# Sch_ma-reflex.net
KiCad netlist of a schematic drawn in EasyEDA
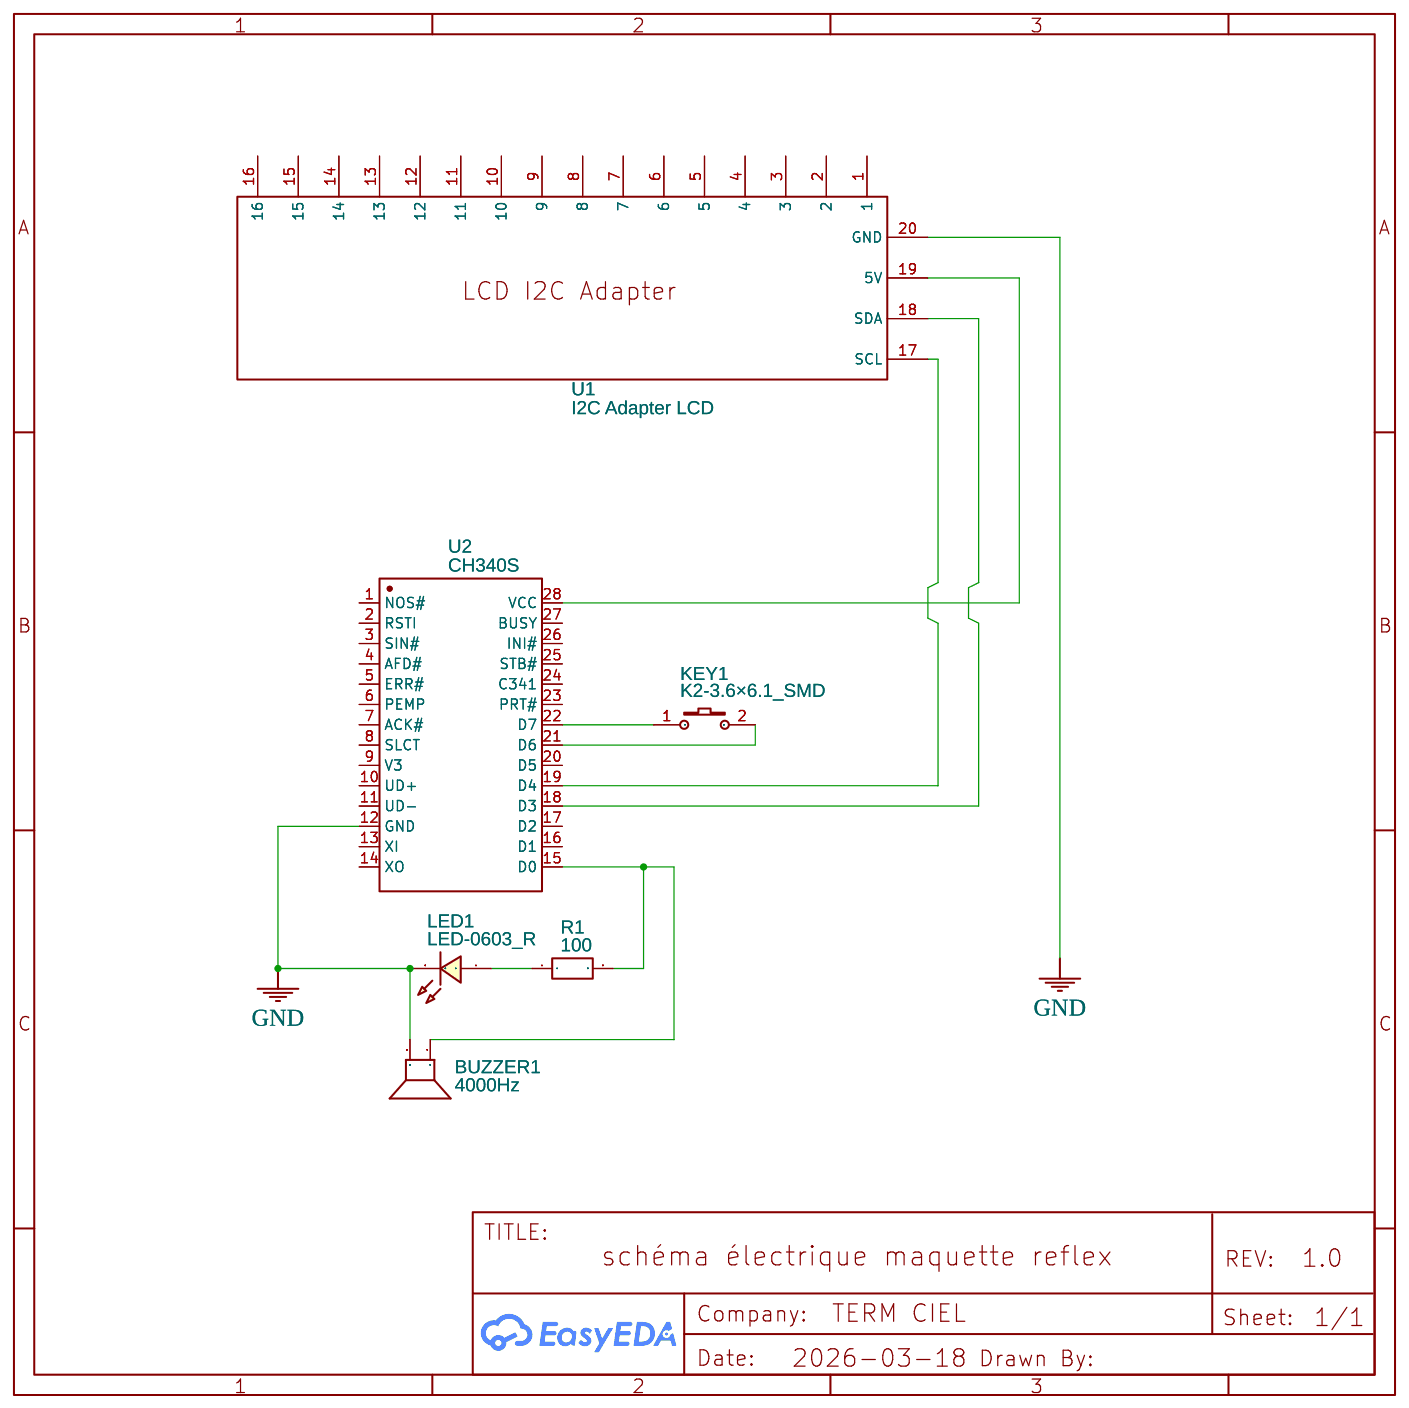
[diagram p0: schematic sheet]

(export (version "E")
  (design (tool "Eeschema 10.0.6"))
  (components
    (comp (ref "BUZZER1")
      (value "4000Hz")
      (fields (field (name "Manufacturer Part") "SFN-1407PA7.6") (field (name "Manufacturer") "S&S(海旭)"))
      (libsource (lib "") (part "SFN-1407PA7.6"))
    )
    (comp (ref "KEY1")
      (value "K2-3.6×6.1_SMD")
      (fields (field (name "Manufacturer Part") "K2-1107ST-A4SW-06"))
      (libsource (lib "") (part "K2-3.6×6.1_SMD"))
    )
    (comp (ref "LED1")
      (value "LED-0603_R")
      (fields
        (field (name "Manufacturer Part") "19-217/R6C-AL1M2VY/3T")
        (field (name "Manufacturer") "EVERLIGHT(台湾亿光)")
      )
      (libsource (lib "") (part "LED-0603_R"))
    )
    (comp (ref "R1") (value "100") (libsource (lib "") (part "R_0603_EU")))
    (comp (ref "U1") (value "I2C Adapter LCD") (libsource (lib "") (part "I2C Adapter LCD")))
    (comp (ref "U2")
      (value "CH340S")
      (fields (field (name "Manufacturer") "WCH(南京沁恒)"))
      (libsource (lib "") (part "CH340S"))
    )
  )
  (nets
    (net (code "1") (name "GND") (class "Default")
      (node (ref "BUZZER1") (pin "2") (pinfunction "2_2") (pintype "unspecified"))
      (node (ref "LED1") (pin "2") (pinfunction "2_2") (pintype "unspecified"))
      (node (ref "U1") (pin "20") (pinfunction "GND_20") (pintype "unspecified"))
      (node (ref "U2") (pin "12") (pinfunction "GND_12") (pintype "unspecified"))
    )
    (net (code "2") (name "Net-(LED1-Pad1)") (class "Default")
      (node (ref "LED1") (pin "1") (pinfunction "1_1") (pintype "unspecified"))
      (node (ref "R1") (pin "1") (pinfunction "1_1") (pintype "unspecified"))
    )
    (net (code "3") (name "Net-(U1-5V)") (class "Default")
      (node (ref "U1") (pin "19") (pinfunction "5V_19") (pintype "unspecified"))
      (node (ref "U2") (pin "28") (pinfunction "VCC_28") (pintype "unspecified"))
    )
    (net (code "4") (name "Net-(U1-SCL)") (class "Default")
      (node (ref "U1") (pin "17") (pinfunction "SCL_17") (pintype "unspecified"))
      (node (ref "U2") (pin "19") (pinfunction "D4_19") (pintype "unspecified"))
    )
    (net (code "5") (name "Net-(U1-SDA)") (class "Default")
      (node (ref "U1") (pin "18") (pinfunction "SDA_18") (pintype "unspecified"))
      (node (ref "U2") (pin "18") (pinfunction "D3_18") (pintype "unspecified"))
    )
    (net (code "6") (name "Net-(U2-D0)") (class "Default")
      (node (ref "BUZZER1") (pin "1") (pinfunction "1_1") (pintype "unspecified"))
      (node (ref "R1") (pin "2") (pinfunction "2_2") (pintype "unspecified"))
      (node (ref "U2") (pin "15") (pinfunction "D0_15") (pintype "unspecified"))
    )
    (net (code "7") (name "Net-(U2-D6)") (class "Default")
      (node (ref "KEY1") (pin "2") (pinfunction "2_2") (pintype "unspecified"))
      (node (ref "U2") (pin "21") (pinfunction "D6_21") (pintype "unspecified"))
    )
    (net (code "8") (name "Net-(U2-D7)") (class "Default")
      (node (ref "KEY1") (pin "1") (pinfunction "1_1") (pintype "unspecified"))
      (node (ref "U2") (pin "22") (pinfunction "D7_22") (pintype "unspecified"))
    )
    (net (code "9") (name "unconnected-(U1-Pad1)") (class "Default")
      (node (ref "U1") (pin "1") (pinfunction "1_1") (pintype "unspecified"))
    )
    (net (code "10") (name "unconnected-(U1-Pad2)") (class "Default")
      (node (ref "U1") (pin "2") (pinfunction "2_2") (pintype "unspecified"))
    )
    (net (code "11") (name "unconnected-(U1-Pad3)") (class "Default")
      (node (ref "U1") (pin "3") (pinfunction "3_3") (pintype "unspecified"))
    )
    (net (code "12") (name "unconnected-(U1-Pad4)") (class "Default")
      (node (ref "U1") (pin "4") (pinfunction "4_4") (pintype "unspecified"))
    )
    (net (code "13") (name "unconnected-(U1-Pad5)") (class "Default")
      (node (ref "U1") (pin "5") (pinfunction "5_5") (pintype "unspecified"))
    )
    (net (code "14") (name "unconnected-(U1-Pad6)") (class "Default")
      (node (ref "U1") (pin "6") (pinfunction "6_6") (pintype "unspecified"))
    )
    (net (code "15") (name "unconnected-(U1-Pad7)") (class "Default")
      (node (ref "U1") (pin "7") (pinfunction "7_7") (pintype "unspecified"))
    )
    (net (code "16") (name "unconnected-(U1-Pad8)") (class "Default")
      (node (ref "U1") (pin "8") (pinfunction "8_8") (pintype "unspecified"))
    )
    (net (code "17") (name "unconnected-(U1-Pad9)") (class "Default")
      (node (ref "U1") (pin "9") (pinfunction "9_9") (pintype "unspecified"))
    )
    (net (code "18") (name "unconnected-(U1-Pad10)") (class "Default")
      (node (ref "U1") (pin "10") (pinfunction "10_10") (pintype "unspecified"))
    )
    (net (code "19") (name "unconnected-(U1-Pad11)") (class "Default")
      (node (ref "U1") (pin "11") (pinfunction "11_11") (pintype "unspecified"))
    )
    (net (code "20") (name "unconnected-(U1-Pad12)") (class "Default")
      (node (ref "U1") (pin "12") (pinfunction "12_12") (pintype "unspecified"))
    )
    (net (code "21") (name "unconnected-(U1-Pad13)") (class "Default")
      (node (ref "U1") (pin "13") (pinfunction "13_13") (pintype "unspecified"))
    )
    (net (code "22") (name "unconnected-(U1-Pad14)") (class "Default")
      (node (ref "U1") (pin "14") (pinfunction "14_14") (pintype "unspecified"))
    )
    (net (code "23") (name "unconnected-(U1-Pad15)") (class "Default")
      (node (ref "U1") (pin "15") (pinfunction "15_15") (pintype "unspecified"))
    )
    (net (code "24") (name "unconnected-(U1-Pad16)") (class "Default")
      (node (ref "U1") (pin "16") (pinfunction "16_16") (pintype "unspecified"))
    )
    (net (code "25") (name "unconnected-(U2-ACK#-Pad7)") (class "Default")
      (node (ref "U2") (pin "7") (pinfunction "ACK#_7") (pintype "unspecified"))
    )
    (net (code "26") (name "unconnected-(U2-AFD#-Pad4)") (class "Default")
      (node (ref "U2") (pin "4") (pinfunction "AFD#_4") (pintype "unspecified"))
    )
    (net (code "27") (name "unconnected-(U2-BUSY-Pad27)") (class "Default")
      (node (ref "U2") (pin "27") (pinfunction "BUSY_27") (pintype "unspecified"))
    )
    (net (code "28") (name "unconnected-(U2-C341-Pad24)") (class "Default")
      (node (ref "U2") (pin "24") (pinfunction "C341_24") (pintype "unspecified"))
    )
    (net (code "29") (name "unconnected-(U2-D1-Pad16)") (class "Default")
      (node (ref "U2") (pin "16") (pinfunction "D1_16") (pintype "unspecified"))
    )
    (net (code "30") (name "unconnected-(U2-D2-Pad17)") (class "Default")
      (node (ref "U2") (pin "17") (pinfunction "D2_17") (pintype "unspecified"))
    )
    (net (code "31") (name "unconnected-(U2-D5-Pad20)") (class "Default")
      (node (ref "U2") (pin "20") (pinfunction "D5_20") (pintype "unspecified"))
    )
    (net (code "32") (name "unconnected-(U2-ERR#-Pad5)") (class "Default")
      (node (ref "U2") (pin "5") (pinfunction "ERR#_5") (pintype "unspecified"))
    )
    (net (code "33") (name "unconnected-(U2-INI#-Pad26)") (class "Default")
      (node (ref "U2") (pin "26") (pinfunction "INI#_26") (pintype "unspecified"))
    )
    (net (code "34") (name "unconnected-(U2-NOS#-Pad1)") (class "Default")
      (node (ref "U2") (pin "1") (pinfunction "NOS#_1") (pintype "unspecified"))
    )
    (net (code "35") (name "unconnected-(U2-PEMP-Pad6)") (class "Default")
      (node (ref "U2") (pin "6") (pinfunction "PEMP_6") (pintype "unspecified"))
    )
    (net (code "36") (name "unconnected-(U2-PRT#-Pad23)") (class "Default")
      (node (ref "U2") (pin "23") (pinfunction "PRT#_23") (pintype "unspecified"))
    )
    (net (code "37") (name "unconnected-(U2-RSTI-Pad2)") (class "Default")
      (node (ref "U2") (pin "2") (pinfunction "RSTI_2") (pintype "unspecified"))
    )
    (net (code "38") (name "unconnected-(U2-SIN#-Pad3)") (class "Default")
      (node (ref "U2") (pin "3") (pinfunction "SIN#_3") (pintype "unspecified"))
    )
    (net (code "39") (name "unconnected-(U2-SLCT-Pad8)") (class "Default")
      (node (ref "U2") (pin "8") (pinfunction "SLCT_8") (pintype "unspecified"))
    )
    (net (code "40") (name "unconnected-(U2-STB#-Pad25)") (class "Default")
      (node (ref "U2") (pin "25") (pinfunction "STB#_25") (pintype "unspecified"))
    )
    (net (code "41") (name "unconnected-(U2-UD+-Pad10)") (class "Default")
      (node (ref "U2") (pin "10") (pinfunction "UD+_10") (pintype "unspecified"))
    )
    (net (code "42") (name "unconnected-(U2-UD--Pad11)") (class "Default")
      (node (ref "U2") (pin "11") (pinfunction "UD-_11") (pintype "unspecified"))
    )
    (net (code "43") (name "unconnected-(U2-V3-Pad9)") (class "Default")
      (node (ref "U2") (pin "9") (pinfunction "V3_9") (pintype "unspecified"))
    )
    (net (code "44") (name "unconnected-(U2-XI-Pad13)") (class "Default")
      (node (ref "U2") (pin "13") (pinfunction "XI_13") (pintype "unspecified"))
    )
    (net (code "45") (name "unconnected-(U2-XO-Pad14)") (class "Default")
      (node (ref "U2") (pin "14") (pinfunction "XO_14") (pintype "unspecified"))
    )
  )
)
